# DAC_Schematic.net
KiCad netlist of a schematic drawn in Altium Designer
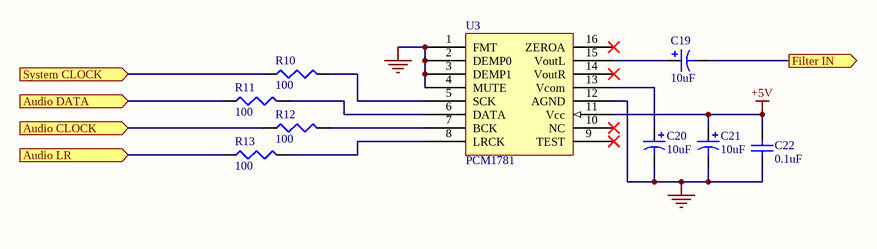
[diagram p0: DAC.Schematic.SchDoc]

(export (version "E")
  (design (tool "Eeschema 10.0.6"))
  (components
    (comp (ref "C19")
      (value "10uF")
      (footprint "CAPC1608N")
      (description "Polarized Capacitor (Radial)")
      (fields (field (name "PUBLISHER") "Altium Limited"))
      (libsource (lib "Miscellaneous Devices") (part "Cap Pol1"))
    )
    (comp (ref "C20")
      (value "10uF")
      (footprint "CAPC1608N")
      (description "Polarized Capacitor (Radial)")
      (fields (field (name "PUBLISHER") "Altium Limited"))
      (libsource (lib "Miscellaneous Devices") (part "Cap Pol1"))
    )
    (comp (ref "C21")
      (value "10uF")
      (footprint "CAPC1608N")
      (description "Polarized Capacitor (Radial)")
      (fields (field (name "PUBLISHER") "Altium Limited"))
      (libsource (lib "Miscellaneous Devices") (part "Cap Pol1"))
    )
    (comp (ref "C22")
      (value "0.1uF")
      (footprint "CAPC1608N")
      (description "Capacitor (Semiconductor SIM Model)")
      (fields (field (name "PUBLISHER") "Altium Limited"))
      (libsource (lib "Miscellaneous Devices") (part "Cap Semi"))
    )
    (comp (ref "R10")
      (value "100")
      (footprint "CAPC1608N")
      (description "Resistor")
      (fields (field (name "PUBLISHER") "Altium Limited"))
      (libsource (lib "Miscellaneous Devices") (part "Res3"))
    )
    (comp (ref "R11")
      (value "100")
      (footprint "CAPC1608N")
      (description "Resistor")
      (fields (field (name "PUBLISHER") "Altium Limited"))
      (libsource (lib "Miscellaneous Devices") (part "Res3"))
    )
    (comp (ref "R12")
      (value "100")
      (footprint "CAPC1608N")
      (description "Resistor")
      (fields (field (name "PUBLISHER") "Altium Limited"))
      (libsource (lib "Miscellaneous Devices") (part "Res3"))
    )
    (comp (ref "R13")
      (value "100")
      (footprint "CAPC1608N")
      (description "Resistor")
      (fields (field (name "PUBLISHER") "Altium Limited"))
      (libsource (lib "Miscellaneous Devices") (part "Res3"))
    )
    (comp (ref "U3")
      (value "PCM1781")
      (footprint "PCM1781")
      (libsource (lib "SynthyTwo.Components") (part "PCM1781 DAC"))
    )
  )
  (nets
    (net (code "1") (name "+5V") (class "Default")
      (node (ref "C21") (pin "1") (pinfunction "1_1") (pintype "passive"))
      (node (ref "C22") (pin "2") (pinfunction "2_2") (pintype "passive"))
      (node (ref "U3") (pin "11") (pinfunction "Vcc_11") (pintype "input"))
    )
    (net (code "2") (name "/Audio CLOCK") (class "Default")
      (node (ref "R12") (pin "1") (pinfunction "1_1") (pintype "passive"))
    )
    (net (code "3") (name "/Audio DATA") (class "Default")
      (node (ref "R11") (pin "1") (pinfunction "1_1") (pintype "passive"))
    )
    (net (code "4") (name "/Audio LR") (class "Default")
      (node (ref "R13") (pin "1") (pinfunction "1_1") (pintype "passive"))
    )
    (net (code "5") (name "/Filter IN") (class "Default")
      (node (ref "C19") (pin "2") (pinfunction "2_2") (pintype "passive"))
    )
    (net (code "6") (name "/System CLOCK") (class "Default")
      (node (ref "R10") (pin "1") (pinfunction "1_1") (pintype "passive"))
    )
    (net (code "7") (name "<NO NET>") (class "Default")
      (node (ref "C20") (pin "2") (pinfunction "2_2") (pintype "passive"))
      (node (ref "C21") (pin "2") (pinfunction "2_2") (pintype "passive"))
      (node (ref "C22") (pin "1") (pinfunction "1_1") (pintype "passive"))
      (node (ref "U3") (pin "1") (pinfunction "FMT_1") (pintype "passive"))
      (node (ref "U3") (pin "12") (pinfunction "AGND_12") (pintype "passive"))
      (node (ref "U3") (pin "2") (pinfunction "DEMP0_2") (pintype "passive"))
      (node (ref "U3") (pin "3") (pinfunction "DEMP1_3") (pintype "passive"))
      (node (ref "U3") (pin "4") (pinfunction "MUTE_4") (pintype "passive"))
    )
    (net (code "8") (name "Net-(U3-BCK)") (class "Default")
      (node (ref "R12") (pin "2") (pinfunction "2_2") (pintype "passive"))
      (node (ref "U3") (pin "7") (pinfunction "BCK_7") (pintype "passive"))
    )
    (net (code "9") (name "Net-(U3-DATA)") (class "Default")
      (node (ref "R11") (pin "2") (pinfunction "2_2") (pintype "passive"))
      (node (ref "U3") (pin "6") (pinfunction "DATA_6") (pintype "passive"))
    )
    (net (code "10") (name "Net-(U3-LRCK)") (class "Default")
      (node (ref "R13") (pin "2") (pinfunction "2_2") (pintype "passive"))
      (node (ref "U3") (pin "8") (pinfunction "LRCK_8") (pintype "passive"))
    )
    (net (code "11") (name "Net-(U3-SCK)") (class "Default")
      (node (ref "R10") (pin "2") (pinfunction "2_2") (pintype "passive"))
      (node (ref "U3") (pin "5") (pinfunction "SCK_5") (pintype "passive"))
    )
    (net (code "12") (name "Net-(U3-Vcom)") (class "Default")
      (node (ref "C20") (pin "1") (pinfunction "1_1") (pintype "passive"))
      (node (ref "U3") (pin "13") (pinfunction "Vcom_13") (pintype "passive"))
    )
    (net (code "13") (name "Net-(U3-VoutL)") (class "Default")
      (node (ref "C19") (pin "1") (pinfunction "1_1") (pintype "passive"))
      (node (ref "U3") (pin "15") (pinfunction "VoutL_15") (pintype "passive"))
    )
    (net (code "14") (name "unconnected-(U3-NC-Pad10)") (class "Default")
      (node (ref "U3") (pin "10") (pinfunction "NC_10") (pintype "passive+no_connect"))
    )
    (net (code "15") (name "unconnected-(U3-TEST-Pad9)") (class "Default")
      (node (ref "U3") (pin "9") (pinfunction "TEST_9") (pintype "passive+no_connect"))
    )
    (net (code "16") (name "unconnected-(U3-VoutR-Pad14)") (class "Default")
      (node (ref "U3") (pin "14") (pinfunction "VoutR_14") (pintype "passive+no_connect"))
    )
    (net (code "17") (name "unconnected-(U3-ZEROA-Pad16)") (class "Default")
      (node (ref "U3") (pin "16") (pinfunction "ZEROA_16") (pintype "passive+no_connect"))
    )
  )
)
